# rx_mod.net
KiCad netlist of a schematic drawn in EAGLE
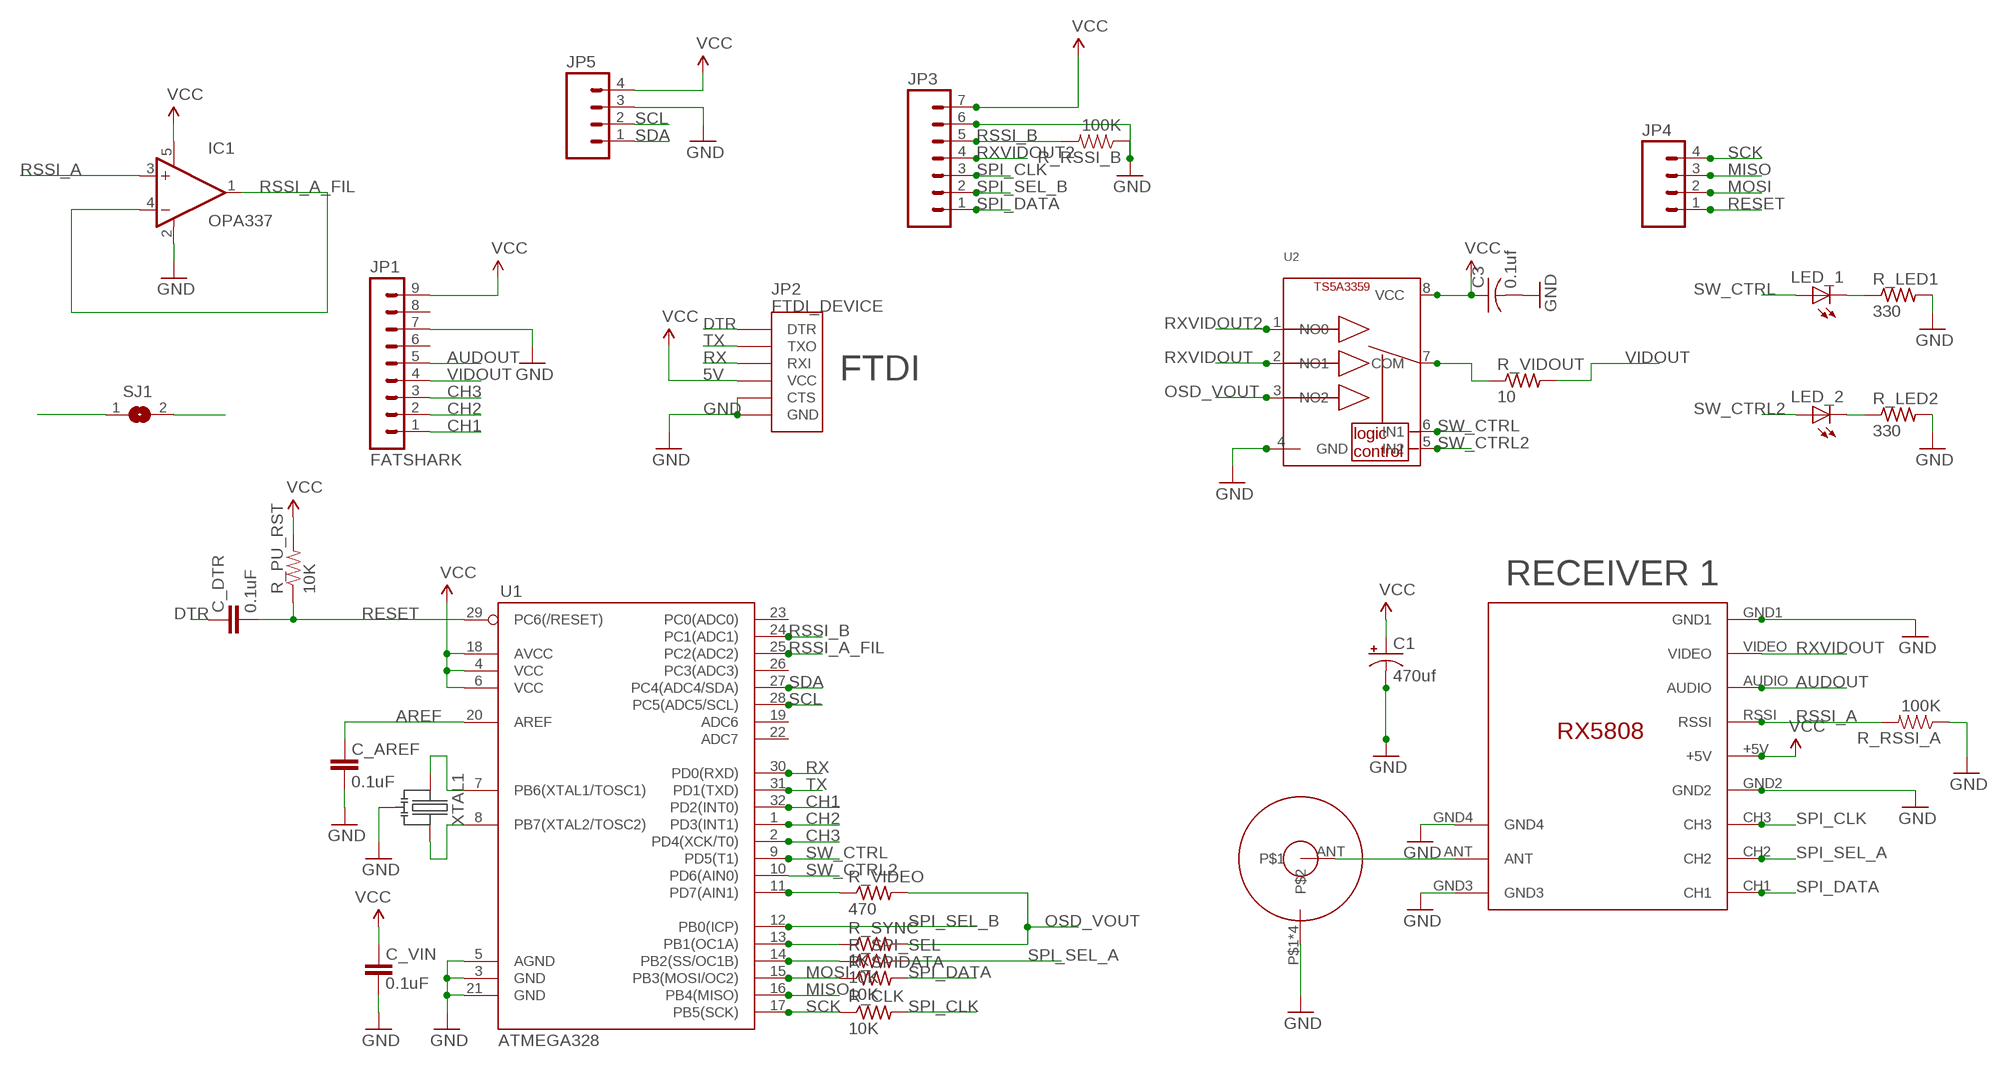
[diagram p0: schematic, sheet 1]

(export (version "E")
  (design (tool "Eeschema 10.0.6"))
  (components
    (comp (ref "C1")
      (value "470uf")
      (footprint "eagle-import:EIA7343")
      (libsource (lib "eagle-import") (part "CAP_POL7343"))
    )
    (comp (ref "C3")
      (value "0.1uf")
      (footprint "eagle-import:C0603")
      (libsource (lib "eagle-import") (part "C-USC0603"))
    )
    (comp (ref "C_AREF")
      (value "0.1uF")
      (footprint "eagle-import:0603-CAP")
      (libsource (lib "eagle-import") (part "CAP0603-CAP"))
    )
    (comp (ref "C_DTR")
      (value "0.1uF")
      (footprint "eagle-import:0603-CAP")
      (libsource (lib "eagle-import") (part "CAP0603-CAP"))
    )
    (comp (ref "C_VIN")
      (value "0.1uF")
      (footprint "eagle-import:0603-CAP")
      (libsource (lib "eagle-import") (part "CAP0603-CAP"))
    )
    (comp (ref "IC1")
      (value "OPA336N")
      (footprint "eagle-import:SOT23-5")
      (fields (field (name "MPN") "OPA336NA"))
      (libsource (lib "eagle-import") (part "OPA336N"))
    )
    (comp (ref "JP1")
      (value "FATSHARK")
      (footprint "eagle-import:MA09-1")
      (libsource (lib "eagle-import") (part "MA09-1"))
    )
    (comp (ref "JP2")
      (value "FTDI_DEVICE")
      (footprint "eagle-import:FTDI_DEVICE_SIDE")
      (libsource (lib "eagle-import") (part "FTDI_DEVICE"))
    )
    (comp (ref "JP3")
      (value "M07")
      (footprint "eagle-import:1X07")
      (libsource (lib "eagle-import") (part "M07"))
    )
    (comp (ref "JP4")
      (value "M04PTH")
      (footprint "eagle-import:1X04")
      (libsource (lib "eagle-import") (part "M04PTH"))
    )
    (comp (ref "JP5")
      (value "M04PTH")
      (footprint "eagle-import:1X04")
      (libsource (lib "eagle-import") (part "M04PTH"))
    )
    (comp (ref "LED_1")
      (value "LEDSML0603")
      (footprint "eagle-import:SML0603")
      (libsource (lib "eagle-import") (part "LEDSML0603"))
    )
    (comp (ref "LED_2")
      (value "LEDSML0603")
      (footprint "eagle-import:SML0603")
      (libsource (lib "eagle-import") (part "LEDSML0603"))
    )
    (comp (ref "RECEIVER_A")
      (value "RX5808_A")
      (footprint "eagle-import:RX5808")
      (libsource (lib "eagle-import") (part "RX5808"))
    )
    (comp (ref "R_CLK")
      (value "10K")
      (footprint "eagle-import:R0805")
      (libsource (lib "eagle-import") (part "R-US_R0805"))
    )
    (comp (ref "R_LED1")
      (value "330")
      (footprint "eagle-import:R0603")
      (libsource (lib "eagle-import") (part "R-US_R0603"))
    )
    (comp (ref "R_LED2")
      (value "330")
      (footprint "eagle-import:R0603")
      (libsource (lib "eagle-import") (part "R-US_R0603"))
    )
    (comp (ref "R_PU_RST")
      (value "10K")
      (footprint "eagle-import:0603-RES")
      (libsource (lib "eagle-import") (part "RESISTOR0603-RES"))
    )
    (comp (ref "R_RSSI_A")
      (value "100K")
      (footprint "eagle-import:0603-RES")
      (libsource (lib "eagle-import") (part "RESISTOR0603-RES"))
    )
    (comp (ref "R_RSSI_B")
      (value "100K")
      (footprint "eagle-import:0603-RES")
      (libsource (lib "eagle-import") (part "RESISTOR0603-RES"))
    )
    (comp (ref "R_SPIDATA")
      (value "10K")
      (footprint "eagle-import:R0805")
      (libsource (lib "eagle-import") (part "R-US_R0805"))
    )
    (comp (ref "R_SPI_SEL")
      (value "10K")
      (footprint "eagle-import:R0805")
      (libsource (lib "eagle-import") (part "R-US_R0805"))
    )
    (comp (ref "R_SYNC")
      (value "1K")
      (footprint "eagle-import:R0805")
      (libsource (lib "eagle-import") (part "R-US_R0805"))
    )
    (comp (ref "R_VIDEO")
      (value "470")
      (footprint "eagle-import:R0805")
      (libsource (lib "eagle-import") (part "R-US_R0805"))
    )
    (comp (ref "R_VIDOUT")
      (value "10")
      (footprint "eagle-import:R0805")
      (libsource (lib "eagle-import") (part "R-US_R0805"))
    )
    (comp (ref "SJ1") (value "SJ") (footprint "eagle-import:SJ") (libsource (lib "eagle-import") (part "SJ")))
    (comp (ref "U$1")
      (value "SMA_ANTENNA")
      (footprint "eagle-import:SMA_CONNECTOR")
      (libsource (lib "eagle-import") (part "SMA_ANTENNA"))
    )
    (comp (ref "U1")
      (value "ATMEGA328")
      (footprint "eagle-import:TQFP32-08")
      (libsource (lib "eagle-import") (part "ATMEGA168"))
    )
    (comp (ref "U2")
      (value "TS5A3359")
      (footprint "eagle-import:VFSOP-8")
      (libsource (lib "eagle-import") (part "TS5A3359"))
    )
    (comp (ref "XTAL1")
      (value "CSTCE16M0V53-R0")
      (footprint "eagle-import:CSTCE16M0V53-R0")
      (libsource (lib "eagle-import") (part "CSTCE16M0V53-R0"))
    )
  )
  (nets
    (net (code "1") (name "/AREF") (class "Default")
      (node (ref "C_AREF") (pin "2") (pinfunction "2_2") (pintype "passive"))
      (node (ref "U1") (pin "20") (pinfunction "AREF_20") (pintype "bidirectional"))
    )
    (net (code "2") (name "/AUDOUT") (class "Default")
      (node (ref "JP1") (pin "5") (pinfunction "5_5") (pintype "passive"))
      (node (ref "RECEIVER_A") (pin "AUDIO") (pinfunction "AUDIO_AUDIO") (pintype "bidirectional"))
    )
    (net (code "3") (name "/CH1") (class "Default")
      (node (ref "JP1") (pin "1") (pinfunction "1_1") (pintype "passive"))
      (node (ref "U1") (pin "32") (pinfunction "PD2(INT0)_32") (pintype "bidirectional"))
    )
    (net (code "4") (name "/CH2") (class "Default")
      (node (ref "JP1") (pin "2") (pinfunction "2_2") (pintype "passive"))
      (node (ref "U1") (pin "1") (pinfunction "PD3(INT1)_1") (pintype "bidirectional"))
    )
    (net (code "5") (name "/CH3") (class "Default")
      (node (ref "JP1") (pin "3") (pinfunction "3_3") (pintype "passive"))
      (node (ref "U1") (pin "2") (pinfunction "PD4(XCK/T0)_2") (pintype "bidirectional"))
    )
    (net (code "6") (name "/DTR") (class "Default")
      (node (ref "C_DTR") (pin "2") (pinfunction "2_2") (pintype "passive"))
      (node (ref "JP2") (pin "P$1") (pinfunction "DTR_P$1") (pintype "bidirectional"))
    )
    (net (code "7") (name "/MISO") (class "Default")
      (node (ref "JP4") (pin "3") (pinfunction "3_3") (pintype "passive"))
      (node (ref "U1") (pin "16") (pinfunction "PB4(MISO)_16") (pintype "bidirectional"))
    )
    (net (code "8") (name "/MOSI") (class "Default")
      (node (ref "JP4") (pin "2") (pinfunction "2_2") (pintype "passive"))
      (node (ref "R_SPIDATA") (pin "1") (pinfunction "1_1") (pintype "passive"))
      (node (ref "U1") (pin "15") (pinfunction "PB3(MOSI/OC2)_15") (pintype "bidirectional"))
    )
    (net (code "9") (name "/OSD_VOUT") (class "Default")
      (node (ref "R_SYNC") (pin "2") (pinfunction "2_2") (pintype "passive"))
      (node (ref "R_VIDEO") (pin "2") (pinfunction "2_2") (pintype "passive"))
      (node (ref "U2") (pin "3") (pinfunction "NO2_3") (pintype "input"))
    )
    (net (code "10") (name "/RESET") (class "Default")
      (node (ref "C_DTR") (pin "1") (pinfunction "1_1") (pintype "passive"))
      (node (ref "JP4") (pin "1") (pinfunction "1_1") (pintype "passive"))
      (node (ref "R_PU_RST") (pin "1") (pinfunction "1_1") (pintype "passive"))
      (node (ref "U1") (pin "29") (pinfunction "PC6(/RESET)_29") (pintype "bidirectional"))
    )
    (net (code "11") (name "/RSSI_A") (class "Default")
      (node (ref "IC1") (pin "3") (pinfunction "+IN_3") (pintype "input"))
      (node (ref "RECEIVER_A") (pin "RSSI") (pinfunction "RSSI_RSSI") (pintype "bidirectional"))
      (node (ref "R_RSSI_A") (pin "2") (pinfunction "2_2") (pintype "passive"))
      (node (ref "SJ1") (pin "1") (pinfunction "1_1") (pintype "passive"))
    )
    (net (code "12") (name "/RSSI_A_FIL") (class "Default")
      (node (ref "IC1") (pin "1") (pinfunction "OUT_1") (pintype "output"))
      (node (ref "IC1") (pin "4") (pinfunction "-IN_4") (pintype "input"))
      (node (ref "SJ1") (pin "2") (pinfunction "2_2") (pintype "passive"))
      (node (ref "U1") (pin "25") (pinfunction "PC2(ADC2)_25") (pintype "bidirectional"))
    )
    (net (code "13") (name "/RSSI_B") (class "Default")
      (node (ref "JP3") (pin "5") (pinfunction "5_5") (pintype "passive"))
      (node (ref "R_RSSI_B") (pin "2") (pinfunction "2_2") (pintype "passive"))
      (node (ref "U1") (pin "24") (pinfunction "PC1(ADC1)_24") (pintype "bidirectional"))
    )
    (net (code "14") (name "/RX") (class "Default")
      (node (ref "JP2") (pin "P$3") (pinfunction "RXI_P$3") (pintype "bidirectional"))
      (node (ref "U1") (pin "30") (pinfunction "PD0(RXD)_30") (pintype "bidirectional"))
    )
    (net (code "15") (name "/RXVIDOUT") (class "Default")
      (node (ref "RECEIVER_A") (pin "VIDEO") (pinfunction "VIDEO_VIDEO") (pintype "bidirectional"))
      (node (ref "U2") (pin "2") (pinfunction "NO1_2") (pintype "input"))
    )
    (net (code "16") (name "/RXVIDOUT2") (class "Default")
      (node (ref "JP3") (pin "4") (pinfunction "4_4") (pintype "passive"))
      (node (ref "U2") (pin "1") (pinfunction "NO0_1") (pintype "input"))
    )
    (net (code "17") (name "/SCK") (class "Default")
      (node (ref "JP4") (pin "4") (pinfunction "4_4") (pintype "passive"))
      (node (ref "R_CLK") (pin "1") (pinfunction "1_1") (pintype "passive"))
      (node (ref "U1") (pin "17") (pinfunction "PB5(SCK)_17") (pintype "bidirectional"))
    )
    (net (code "18") (name "/SCL") (class "Default")
      (node (ref "JP5") (pin "2") (pinfunction "2_2") (pintype "passive"))
      (node (ref "U1") (pin "28") (pinfunction "PC5(ADC5/SCL)_28") (pintype "bidirectional"))
    )
    (net (code "19") (name "/SDA") (class "Default")
      (node (ref "JP5") (pin "1") (pinfunction "1_1") (pintype "passive"))
      (node (ref "U1") (pin "27") (pinfunction "PC4(ADC4/SDA)_27") (pintype "bidirectional"))
    )
    (net (code "20") (name "/SPI_CLK") (class "Default")
      (node (ref "JP3") (pin "3") (pinfunction "3_3") (pintype "passive"))
      (node (ref "RECEIVER_A") (pin "CH3") (pinfunction "CH3_CH3") (pintype "bidirectional"))
      (node (ref "R_CLK") (pin "2") (pinfunction "2_2") (pintype "passive"))
    )
    (net (code "21") (name "/SPI_DATA") (class "Default")
      (node (ref "JP3") (pin "1") (pinfunction "1_1") (pintype "passive"))
      (node (ref "RECEIVER_A") (pin "CH1") (pinfunction "CH1_CH1") (pintype "bidirectional"))
      (node (ref "R_SPIDATA") (pin "2") (pinfunction "2_2") (pintype "passive"))
    )
    (net (code "22") (name "/SPI_SEL_A") (class "Default")
      (node (ref "RECEIVER_A") (pin "CH2") (pinfunction "CH2_CH2") (pintype "bidirectional"))
      (node (ref "R_SPI_SEL") (pin "2") (pinfunction "2_2") (pintype "passive"))
    )
    (net (code "23") (name "/SPI_SEL_B") (class "Default")
      (node (ref "JP3") (pin "2") (pinfunction "2_2") (pintype "passive"))
      (node (ref "U1") (pin "12") (pinfunction "PB0(ICP)_12") (pintype "bidirectional"))
    )
    (net (code "24") (name "/SW_CTRL") (class "Default")
      (node (ref "LED_1") (pin "A") (pinfunction "A_A") (pintype "passive"))
      (node (ref "U1") (pin "9") (pinfunction "PD5(T1)_9") (pintype "bidirectional"))
      (node (ref "U2") (pin "6") (pinfunction "IN1_6") (pintype "output"))
    )
    (net (code "25") (name "/SW_CTRL2") (class "Default")
      (node (ref "LED_2") (pin "A") (pinfunction "A_A") (pintype "passive"))
      (node (ref "U1") (pin "10") (pinfunction "PD6(AIN0)_10") (pintype "bidirectional"))
      (node (ref "U2") (pin "5") (pinfunction "IN2_5") (pintype "output"))
    )
    (net (code "26") (name "/TX") (class "Default")
      (node (ref "JP2") (pin "P$2") (pinfunction "TXO_P$2") (pintype "bidirectional"))
      (node (ref "U1") (pin "31") (pinfunction "PD1(TXD)_31") (pintype "bidirectional"))
    )
    (net (code "27") (name "/VIDOUT") (class "Default")
      (node (ref "JP1") (pin "4") (pinfunction "4_4") (pintype "passive"))
      (node (ref "R_VIDOUT") (pin "2") (pinfunction "2_2") (pintype "passive"))
    )
    (net (code "28") (name "GND") (class "Default")
      (node (ref "C1") (pin "C") (pinfunction "-_C") (pintype "passive"))
      (node (ref "C3") (pin "2") (pinfunction "2_2") (pintype "passive"))
      (node (ref "C_AREF") (pin "1") (pinfunction "1_1") (pintype "passive"))
      (node (ref "C_VIN") (pin "1") (pinfunction "1_1") (pintype "passive"))
      (node (ref "IC1") (pin "2") (pinfunction "V-_2") (pintype "power_in"))
      (node (ref "JP1") (pin "7") (pinfunction "7_7") (pintype "passive"))
      (node (ref "JP2") (pin "P$5") (pinfunction "CTS_P$5") (pintype "bidirectional"))
      (node (ref "JP2") (pin "P$6") (pinfunction "GND_P$6") (pintype "bidirectional"))
      (node (ref "JP3") (pin "6") (pinfunction "6_6") (pintype "passive"))
      (node (ref "JP5") (pin "3") (pinfunction "3_3") (pintype "passive"))
      (node (ref "RECEIVER_A") (pin "GND1") (pinfunction "GND1_GND1") (pintype "bidirectional"))
      (node (ref "RECEIVER_A") (pin "GND2") (pinfunction "GND2_GND2") (pintype "bidirectional"))
      (node (ref "RECEIVER_A") (pin "GND3") (pinfunction "GND3_GND3") (pintype "bidirectional"))
      (node (ref "RECEIVER_A") (pin "GND4") (pinfunction "GND4_GND4") (pintype "bidirectional"))
      (node (ref "R_LED1") (pin "2") (pinfunction "2_2") (pintype "passive"))
      (node (ref "R_LED2") (pin "2") (pinfunction "2_2") (pintype "passive"))
      (node (ref "R_RSSI_A") (pin "1") (pinfunction "1_1") (pintype "passive"))
      (node (ref "R_RSSI_B") (pin "1") (pinfunction "1_1") (pintype "passive"))
      (node (ref "U$1") (pin "P$1") (pinfunction "P$2_P$1") (pintype "bidirectional"))
      (node (ref "U$1") (pin "P$2") (pinfunction "P$2_P$2") (pintype "bidirectional"))
      (node (ref "U$1") (pin "P$3") (pinfunction "P$2_P$3") (pintype "bidirectional"))
      (node (ref "U$1") (pin "P$4") (pinfunction "P$2_P$4") (pintype "bidirectional"))
      (node (ref "U1") (pin "21") (pinfunction "GND_21") (pintype "bidirectional"))
      (node (ref "U1") (pin "3") (pinfunction "GND_3") (pintype "bidirectional"))
      (node (ref "U1") (pin "5") (pinfunction "AGND_5") (pintype "bidirectional"))
      (node (ref "U2") (pin "4") (pinfunction "GND_4") (pintype "power_in"))
      (node (ref "XTAL1") (pin "2") (pinfunction "2_2") (pintype "bidirectional"))
    )
    (net (code "29") (name "Net-(LED_1-PadC)") (class "Default")
      (node (ref "LED_1") (pin "C") (pinfunction "C_C") (pintype "passive"))
      (node (ref "R_LED1") (pin "1") (pinfunction "1_1") (pintype "passive"))
    )
    (net (code "30") (name "Net-(LED_2-PadC)") (class "Default")
      (node (ref "LED_2") (pin "C") (pinfunction "C_C") (pintype "passive"))
      (node (ref "R_LED2") (pin "1") (pinfunction "1_1") (pintype "passive"))
    )
    (net (code "31") (name "Net-(U$1-P$1)") (class "Default")
      (node (ref "RECEIVER_A") (pin "ANT") (pinfunction "ANT_ANT") (pintype "bidirectional"))
      (node (ref "U$1") (pin "ANT") (pinfunction "P$1_ANT") (pintype "bidirectional"))
    )
    (net (code "32") (name "Net-(U1-PB1(OC1A))") (class "Default")
      (node (ref "R_SYNC") (pin "1") (pinfunction "1_1") (pintype "passive"))
      (node (ref "U1") (pin "13") (pinfunction "PB1(OC1A)_13") (pintype "bidirectional"))
    )
    (net (code "33") (name "Net-(U1-PB2(SS{slash}OC1B))") (class "Default")
      (node (ref "R_SPI_SEL") (pin "1") (pinfunction "1_1") (pintype "passive"))
      (node (ref "U1") (pin "14") (pinfunction "PB2(SS/OC1B)_14") (pintype "bidirectional"))
    )
    (net (code "34") (name "Net-(U1-PB6(XTAL1{slash}TOSC1))") (class "Default")
      (node (ref "U1") (pin "7") (pinfunction "PB6(XTAL1/TOSC1)_7") (pintype "bidirectional"))
      (node (ref "XTAL1") (pin "1") (pinfunction "1_1") (pintype "bidirectional"))
    )
    (net (code "35") (name "Net-(U1-PB7(XTAL2{slash}TOSC2))") (class "Default")
      (node (ref "U1") (pin "8") (pinfunction "PB7(XTAL2/TOSC2)_8") (pintype "bidirectional"))
      (node (ref "XTAL1") (pin "3") (pinfunction "3_3") (pintype "bidirectional"))
    )
    (net (code "36") (name "Net-(U1-PD7(AIN1))") (class "Default")
      (node (ref "R_VIDEO") (pin "1") (pinfunction "1_1") (pintype "passive"))
      (node (ref "U1") (pin "11") (pinfunction "PD7(AIN1)_11") (pintype "bidirectional"))
    )
    (net (code "37") (name "Net-(U2-COM)") (class "Default")
      (node (ref "R_VIDOUT") (pin "1") (pinfunction "1_1") (pintype "passive"))
      (node (ref "U2") (pin "7") (pinfunction "COM_7") (pintype "input"))
    )
    (net (code "38") (name "VCC") (class "Default")
      (node (ref "C1") (pin "A") (pinfunction "+_A") (pintype "passive"))
      (node (ref "C3") (pin "1") (pinfunction "1_1") (pintype "passive"))
      (node (ref "C_VIN") (pin "2") (pinfunction "2_2") (pintype "passive"))
      (node (ref "IC1") (pin "5") (pinfunction "V+_5") (pintype "power_in"))
      (node (ref "JP1") (pin "9") (pinfunction "9_9") (pintype "passive"))
      (node (ref "JP2") (pin "P$4") (pinfunction "VCC_P$4") (pintype "bidirectional"))
      (node (ref "JP3") (pin "7") (pinfunction "7_7") (pintype "passive"))
      (node (ref "JP5") (pin "4") (pinfunction "4_4") (pintype "passive"))
      (node (ref "RECEIVER_A") (pin "+5V") (pinfunction "+5V_+5V") (pintype "bidirectional"))
      (node (ref "R_PU_RST") (pin "2") (pinfunction "2_2") (pintype "passive"))
      (node (ref "U1") (pin "18") (pinfunction "AVCC_18") (pintype "bidirectional"))
      (node (ref "U1") (pin "4") (pinfunction "VCC_4") (pintype "bidirectional"))
      (node (ref "U1") (pin "6") (pinfunction "VCC_6") (pintype "bidirectional"))
      (node (ref "U2") (pin "8") (pinfunction "VCC_8") (pintype "power_in"))
    )
    (net (code "39") (name "unconnected-(JP1-Pad6)") (class "Default")
      (node (ref "JP1") (pin "6") (pinfunction "6_6") (pintype "passive"))
    )
    (net (code "40") (name "unconnected-(JP1-Pad8)") (class "Default")
      (node (ref "JP1") (pin "8") (pinfunction "8_8") (pintype "passive"))
    )
    (net (code "41") (name "unconnected-(U1-ADC6-Pad19)") (class "Default")
      (node (ref "U1") (pin "19") (pinfunction "ADC6_19") (pintype "bidirectional"))
    )
    (net (code "42") (name "unconnected-(U1-ADC7-Pad22)") (class "Default")
      (node (ref "U1") (pin "22") (pinfunction "ADC7_22") (pintype "bidirectional"))
    )
    (net (code "43") (name "unconnected-(U1-PC0(ADC0)-Pad23)") (class "Default")
      (node (ref "U1") (pin "23") (pinfunction "PC0(ADC0)_23") (pintype "bidirectional"))
    )
    (net (code "44") (name "unconnected-(U1-PC3(ADC3)-Pad26)") (class "Default")
      (node (ref "U1") (pin "26") (pinfunction "PC3(ADC3)_26") (pintype "bidirectional"))
    )
  )
)
